# Blueetooth.net
KiCad netlist of a schematic drawn in Altium Designer
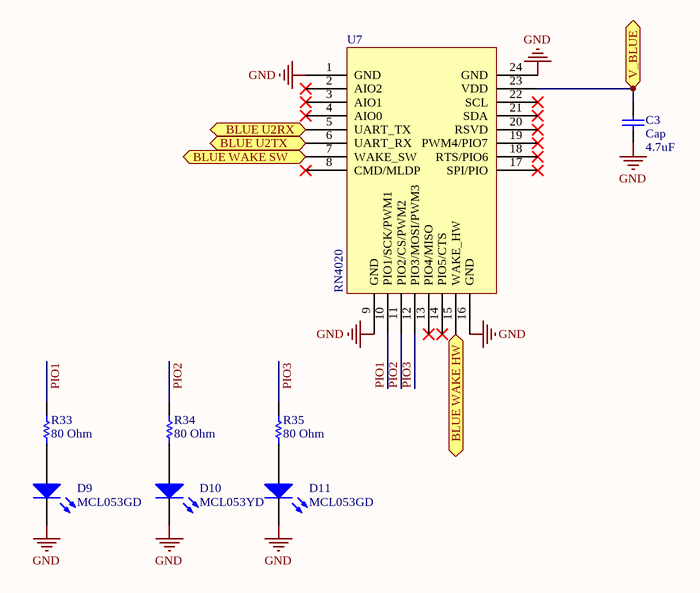
[diagram p0: Blueetooth.SchDoc]

(export (version "E")
  (design (tool "Eeschema 10.0.6"))
  (components
    (comp (ref "C3")
      (value "Cap")
      (footprint "Capacitor")
      (description "Capacitor")
      (fields (field (name "ALTIUM_VALUE") "4.7uF") (field (name "PUBLISHER") "Altium Limited"))
      (libsource (lib "Miscellaneous Devices") (part "Cap"))
    )
    (comp (ref "D9")
      (value "MCL053GD")
      (footprint "LedGreen")
      (description "Typical INFRARED GaAs LED")
      (fields (field (name "PUBLISHER") "Altium Limited"))
      (libsource (lib "Miscellaneous Devices") (part "LED0"))
    )
    (comp (ref "D10")
      (value "MCL053YD")
      (footprint "LedGreen")
      (description "Typical INFRARED GaAs LED")
      (fields (field (name "PUBLISHER") "Altium Limited"))
      (libsource (lib "Miscellaneous Devices") (part "LED0"))
    )
    (comp (ref "D11")
      (value "MCL053GD")
      (footprint "LedGreen")
      (description "Typical INFRARED GaAs LED")
      (fields (field (name "PUBLISHER") "Altium Limited"))
      (libsource (lib "Miscellaneous Devices") (part "LED0"))
    )
    (comp (ref "R33")
      (value "80 Ohm")
      (footprint "Resistor0603")
      (description "Resistor")
      (fields (field (name "PUBLISHER") "Altium Limited"))
      (libsource (lib "Miscellaneous Devices") (part "Res1"))
    )
    (comp (ref "R34")
      (value "80 Ohm")
      (footprint "Resistor0603")
      (description "Resistor")
      (fields (field (name "PUBLISHER") "Altium Limited"))
      (libsource (lib "Miscellaneous Devices") (part "Res1"))
    )
    (comp (ref "R35")
      (value "80 Ohm")
      (footprint "Resistor0603")
      (description "Resistor")
      (fields (field (name "PUBLISHER") "Altium Limited"))
      (libsource (lib "Miscellaneous Devices") (part "Res1"))
    )
    (comp (ref "U7")
      (value "RN4020")
      (footprint "bluetooth")
      (libsource (lib "PROBOT_Schema_Library") (part "Blueetooth"))
    )
  )
  (nets
    (net (code "1") (name "/BLUE U2RX") (class "Default")
      (node (ref "U7") (pin "5") (pinfunction "UART_TX_5") (pintype "passive"))
    )
    (net (code "2") (name "/BLUE U2TX") (class "Default")
      (node (ref "U7") (pin "6") (pinfunction "UART_RX_6") (pintype "passive"))
    )
    (net (code "3") (name "/BLUE WAKE HW") (class "Default")
      (node (ref "U7") (pin "15") (pinfunction "WAKE_HW_15") (pintype "passive"))
    )
    (net (code "4") (name "/BLUE WAKE SW") (class "Default")
      (node (ref "U7") (pin "7") (pinfunction "WAKE_SW_7") (pintype "passive"))
    )
    (net (code "5") (name "/PIO1") (class "Default")
      (node (ref "R33") (pin "2") (pinfunction "2_2") (pintype "passive"))
      (node (ref "U7") (pin "10") (pinfunction "PIO1/SCK/PWM1_10") (pintype "passive"))
    )
    (net (code "6") (name "/PIO2") (class "Default")
      (node (ref "R34") (pin "2") (pinfunction "2_2") (pintype "passive"))
      (node (ref "U7") (pin "11") (pinfunction "PIO2/CS/PWM2_11") (pintype "passive"))
    )
    (net (code "7") (name "/PIO3") (class "Default")
      (node (ref "R35") (pin "2") (pinfunction "2_2") (pintype "passive"))
      (node (ref "U7") (pin "12") (pinfunction "PIO3/MOSI/PWM3_12") (pintype "passive"))
    )
    (net (code "8") (name "/V_BLUE") (class "Default")
      (node (ref "C3") (pin "2") (pinfunction "2_2") (pintype "passive"))
      (node (ref "U7") (pin "23") (pinfunction "VDD_23") (pintype "passive"))
    )
    (net (code "9") (name "GND") (class "Default")
      (node (ref "C3") (pin "1") (pinfunction "1_1") (pintype "passive"))
      (node (ref "D10") (pin "2") (pinfunction "K_2") (pintype "passive"))
      (node (ref "D11") (pin "2") (pinfunction "K_2") (pintype "passive"))
      (node (ref "D9") (pin "2") (pinfunction "K_2") (pintype "passive"))
      (node (ref "U7") (pin "1") (pinfunction "GND_1") (pintype "passive"))
      (node (ref "U7") (pin "16") (pinfunction "GND_16") (pintype "passive"))
      (node (ref "U7") (pin "24") (pinfunction "GND_24") (pintype "passive"))
      (node (ref "U7") (pin "9") (pinfunction "GND_9") (pintype "passive"))
    )
    (net (code "10") (name "Net-(D9-A)") (class "Default")
      (node (ref "D9") (pin "1") (pinfunction "A_1") (pintype "passive"))
      (node (ref "R33") (pin "1") (pinfunction "1_1") (pintype "passive"))
    )
    (net (code "11") (name "Net-(D10-A)") (class "Default")
      (node (ref "D10") (pin "1") (pinfunction "A_1") (pintype "passive"))
      (node (ref "R34") (pin "1") (pinfunction "1_1") (pintype "passive"))
    )
    (net (code "12") (name "Net-(D11-A)") (class "Default")
      (node (ref "D11") (pin "1") (pinfunction "A_1") (pintype "passive"))
      (node (ref "R35") (pin "1") (pinfunction "1_1") (pintype "passive"))
    )
    (net (code "13") (name "unconnected-(U7-AIO0-Pad4)") (class "Default")
      (node (ref "U7") (pin "4") (pinfunction "AIO0_4") (pintype "passive+no_connect"))
    )
    (net (code "14") (name "unconnected-(U7-AIO1-Pad3)") (class "Default")
      (node (ref "U7") (pin "3") (pinfunction "AIO1_3") (pintype "passive+no_connect"))
    )
    (net (code "15") (name "unconnected-(U7-AIO2-Pad2)") (class "Default")
      (node (ref "U7") (pin "2") (pinfunction "AIO2_2") (pintype "passive+no_connect"))
    )
    (net (code "16") (name "unconnected-(U7-CMD{slash}MLDP-Pad8)") (class "Default")
      (node (ref "U7") (pin "8") (pinfunction "CMD/MLDP_8") (pintype "passive+no_connect"))
    )
    (net (code "17") (name "unconnected-(U7-PIO4{slash}MISO-Pad13)") (class "Default")
      (node (ref "U7") (pin "13") (pinfunction "PIO4/MISO_13") (pintype "passive+no_connect"))
    )
    (net (code "18") (name "unconnected-(U7-PIO5{slash}CTS-Pad14)") (class "Default")
      (node (ref "U7") (pin "14") (pinfunction "PIO5/CTS_14") (pintype "passive+no_connect"))
    )
    (net (code "19") (name "unconnected-(U7-PWM4{slash}PIO7-Pad19)") (class "Default")
      (node (ref "U7") (pin "19") (pinfunction "PWM4/PIO7_19") (pintype "passive+no_connect"))
    )
    (net (code "20") (name "unconnected-(U7-RSVD-Pad20)") (class "Default")
      (node (ref "U7") (pin "20") (pinfunction "RSVD_20") (pintype "passive+no_connect"))
    )
    (net (code "21") (name "unconnected-(U7-RTS{slash}PIO6-Pad18)") (class "Default")
      (node (ref "U7") (pin "18") (pinfunction "RTS/PIO6_18") (pintype "passive+no_connect"))
    )
    (net (code "22") (name "unconnected-(U7-SCL-Pad22)") (class "Default")
      (node (ref "U7") (pin "22") (pinfunction "SCL_22") (pintype "passive+no_connect"))
    )
    (net (code "23") (name "unconnected-(U7-SDA-Pad21)") (class "Default")
      (node (ref "U7") (pin "21") (pinfunction "SDA_21") (pintype "passive+no_connect"))
    )
    (net (code "24") (name "unconnected-(U7-SPI{slash}PIO-Pad17)") (class "Default")
      (node (ref "U7") (pin "17") (pinfunction "SPI/PIO_17") (pintype "passive+no_connect"))
    )
  )
)
